# Ideal_Diode_A.net
KiCad netlist of a schematic drawn in Altium Designer
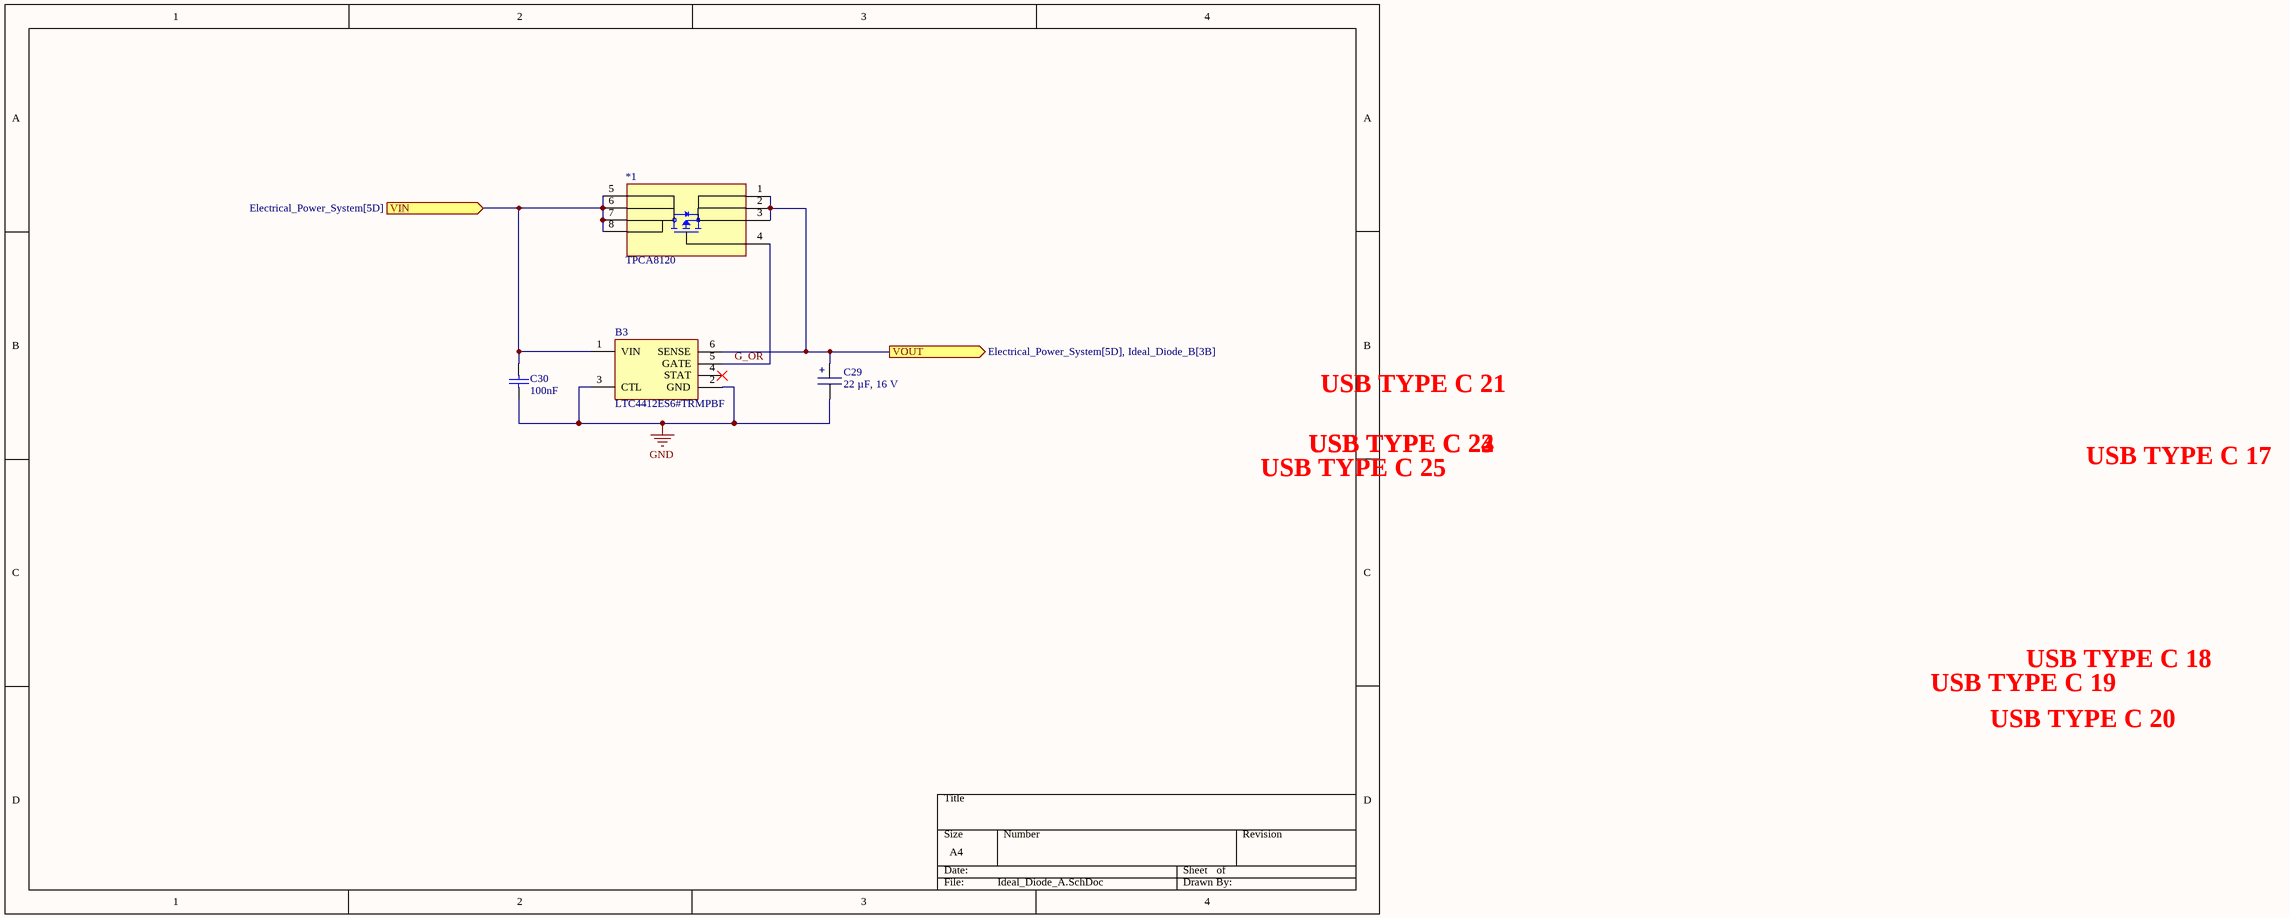
[diagram p0: Ideal_Diode_A.SchDoc]

(export (version "E")
  (design (tool "Eeschema 10.0.6"))
  (components
    (comp (ref "*1")
      (value "TPCA8120")
      (footprint "TRANS_TPHR8504PL,L1Q")
      (libsource (lib "EPS_Board_Lib") (part "TPCA8120"))
    )
    (comp (ref "B3")
      (value "LTC4412ES6#TRMPBF")
      (footprint "SOT95P280X100-6N")
      (description "Hot Swap Controller LTC4412ES6#TRMPBF, Positive Voltage, 2.5  28 V, TSOT-23, 6-Pin")
      (fields (field (name "MOUSER PART NUMBER") "584-LTC4412ES6TRMPBF"))
      (libsource (lib "EPS_Board_Lib") (part "LTC4412ES6"))
    )
    (comp (ref "C29")
      (value "22 µF, 16 V")
      (footprint "TANTALUM SMD C")
      (description "CAP TANT 22uF 10% 16V 2312")
      (libsource (lib "Altium_Tanta_Capacitor") (part "01231222610"))
    )
    (comp (ref "C30")
      (value "100nF")
      (footprint "CAP-SM-0805")
      (description "Capacitor")
      (fields (field (name "Comment") "Cap Non-Pol SMD"))
      (libsource (lib "PIF_Library") (part "Cap Non-Pol SMD"))
    )
  )
  (nets
    (net (code "1") (name "/G_OR") (class "Default")
      (node (ref "*1") (pin "4") (pinfunction "G_4") (pintype "passive"))
      (node (ref "B3") (pin "5") (pinfunction "GATE_5") (pintype "passive"))
    )
    (net (code "2") (name "/VIN") (class "Default")
      (node (ref "*1") (pin "5") (pinfunction "D1_5") (pintype "passive"))
      (node (ref "*1") (pin "6") (pinfunction "D2_6") (pintype "passive"))
      (node (ref "*1") (pin "7") (pinfunction "D3_7") (pintype "passive"))
      (node (ref "*1") (pin "8") (pinfunction "D4_8") (pintype "passive"))
      (node (ref "B3") (pin "1") (pinfunction "VIN_1") (pintype "passive"))
      (node (ref "C30") (pin "2") (pinfunction "2_2") (pintype "passive"))
    )
    (net (code "3") (name "/VOUT") (class "Default")
      (node (ref "*1") (pin "1") (pinfunction "S1_1") (pintype "passive"))
      (node (ref "*1") (pin "2") (pinfunction "S2_2") (pintype "power_in"))
      (node (ref "*1") (pin "3") (pinfunction "S3_3") (pintype "passive"))
      (node (ref "B3") (pin "6") (pinfunction "SENSE_6") (pintype "passive"))
      (node (ref "C29") (pin "2") (pinfunction "2_2") (pintype "passive"))
    )
    (net (code "4") (name "GND") (class "Default")
      (node (ref "B3") (pin "2") (pinfunction "GND_2") (pintype "passive"))
      (node (ref "B3") (pin "3") (pinfunction "CTL_3") (pintype "passive"))
      (node (ref "C29") (pin "1") (pinfunction "1_1") (pintype "passive"))
      (node (ref "C30") (pin "1") (pinfunction "1_1") (pintype "passive"))
    )
    (net (code "5") (name "unconnected-(B3-STAT-Pad4)") (class "Default")
      (node (ref "B3") (pin "4") (pinfunction "STAT_4") (pintype "passive+no_connect"))
    )
  )
)
